# ButtonI2C.net
KiCad netlist of a schematic drawn in EAGLE
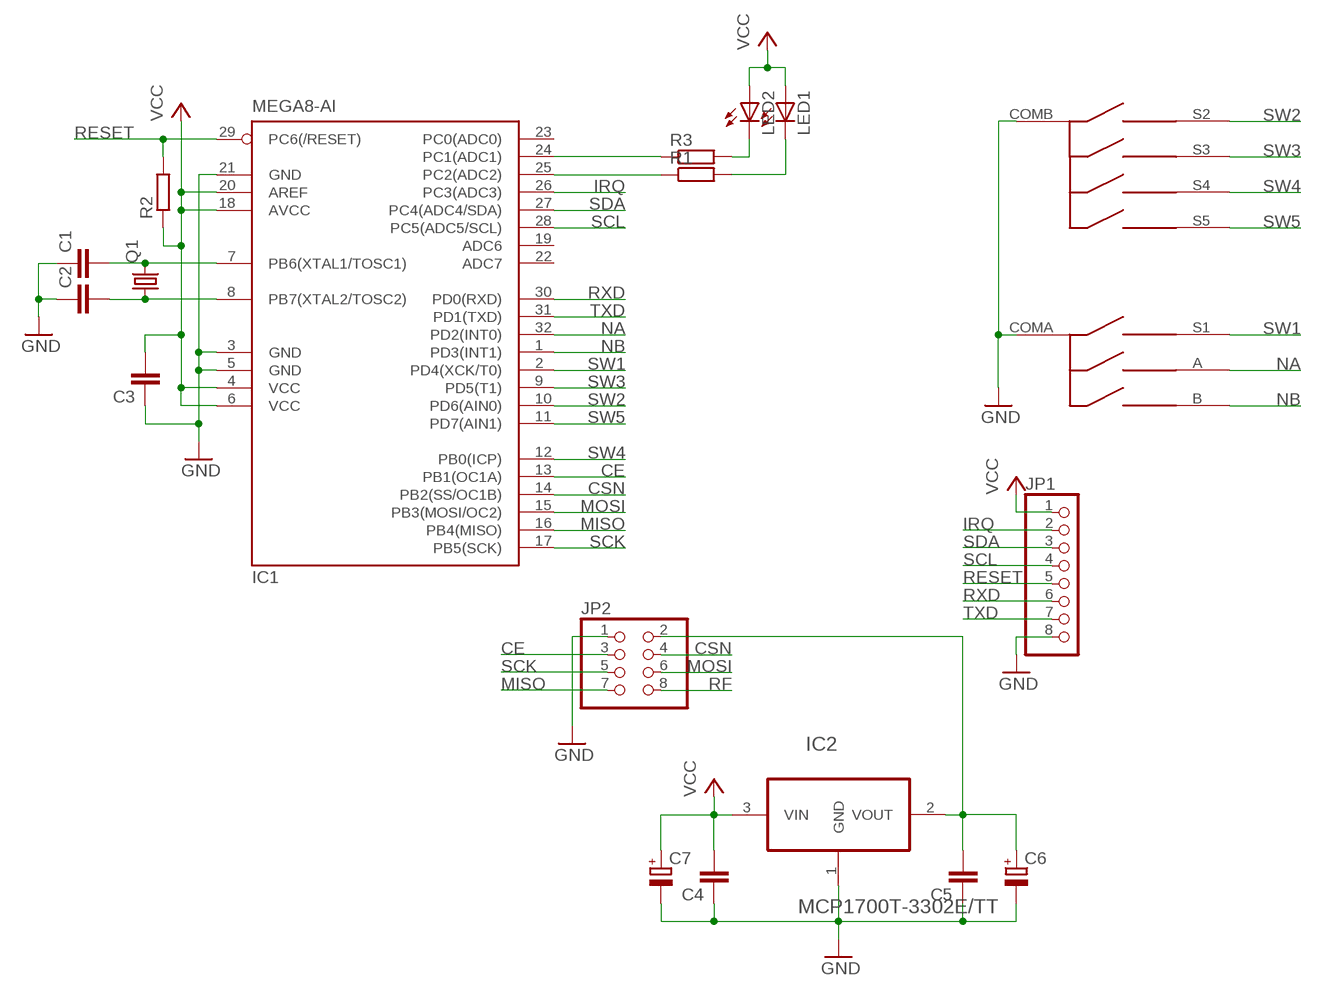
[diagram p0: schematic, sheet 1]

(export (version "E")
  (design (tool "Eeschema 10.0.6"))
  (components
    (comp (ref "C1")
      (value "C-EUC0805K")
      (footprint "eagle-import:C0805K")
      (libsource (lib "eagle-import") (part "C-EUC0805K"))
    )
    (comp (ref "C2")
      (value "C-EUC0805K")
      (footprint "eagle-import:C0805K")
      (libsource (lib "eagle-import") (part "C-EUC0805K"))
    )
    (comp (ref "C3")
      (value "C-EUC0805K")
      (footprint "eagle-import:C0805K")
      (libsource (lib "eagle-import") (part "C-EUC0805K"))
    )
    (comp (ref "C4")
      (value "C-EUC0805K")
      (footprint "eagle-import:C0805K")
      (libsource (lib "eagle-import") (part "C-EUC0805K"))
    )
    (comp (ref "C5")
      (value "C-EUC0805K")
      (footprint "eagle-import:C0805K")
      (libsource (lib "eagle-import") (part "C-EUC0805K"))
    )
    (comp (ref "C6")
      (value "CPOL-EUE2.5-6")
      (footprint "eagle-import:E2,5-6")
      (libsource (lib "eagle-import") (part "CPOL-EUE2.5-6"))
    )
    (comp (ref "C7")
      (value "CPOL-EUE2.5-6")
      (footprint "eagle-import:E2,5-6")
      (libsource (lib "eagle-import") (part "CPOL-EUE2.5-6"))
    )
    (comp (ref "IC1")
      (value "MEGA8-AI")
      (footprint "eagle-import:TQFP32-08")
      (fields (field (name "MPN") "ATMEGA8-16AU"))
      (libsource (lib "eagle-import") (part "MEGA8-AI"))
    )
    (comp (ref "IC2")
      (value "MCP1700T-3302E/TT")
      (footprint "eagle-import:SOT95P237X112-3N")
      (libsource (lib "eagle-import") (part "MCP1700T-3302E/TT"))
    )
    (comp (ref "JP1")
      (value "PINHD-1X8")
      (footprint "eagle-import:1X08")
      (libsource (lib "eagle-import") (part "PINHD-1X8"))
    )
    (comp (ref "JP2")
      (value "PINHD-2X4")
      (footprint "eagle-import:2X04")
      (libsource (lib "eagle-import") (part "PINHD-2X4"))
    )
    (comp (ref "LED1")
      (value "LEDCHIPLED_0805")
      (footprint "eagle-import:CHIPLED_0805")
      (libsource (lib "eagle-import") (part "LEDCHIPLED_0805"))
    )
    (comp (ref "LED2")
      (value "LEDCHIPLED_0805")
      (footprint "eagle-import:CHIPLED_0805")
      (libsource (lib "eagle-import") (part "LEDCHIPLED_0805"))
    )
    (comp (ref "Q1")
      (value "CRYSTALHC49UP")
      (footprint "eagle-import:HC49UP")
      (libsource (lib "eagle-import") (part "CRYSTALHC49UP"))
    )
    (comp (ref "R1")
      (value "R-EU_M0805")
      (footprint "eagle-import:M0805")
      (libsource (lib "eagle-import") (part "R-EU_M0805"))
    )
    (comp (ref "R2")
      (value "R-EU_M0805")
      (footprint "eagle-import:M0805")
      (libsource (lib "eagle-import") (part "R-EU_M0805"))
    )
    (comp (ref "R3")
      (value "R-EU_M0805")
      (footprint "eagle-import:M0805")
      (libsource (lib "eagle-import") (part "R-EU_M0805"))
    )
    (comp (ref "U$1")
      (value "ANO-I1B-M1B-O2B-S-Z")
      (footprint "eagle-import:ANO-I1B-M1B-O2B-S-Z")
      (libsource (lib "eagle-import") (part "ANO-I1B-M1B-O2B-S-Z"))
    )
  )
  (nets
    (net (code "1") (name "/CE") (class "Default")
      (node (ref "IC1") (pin "13") (pinfunction "PB1(OC1A)_13") (pintype "bidirectional"))
      (node (ref "JP2") (pin "3") (pinfunction "3_3") (pintype "passive"))
    )
    (net (code "2") (name "/CSN") (class "Default")
      (node (ref "IC1") (pin "14") (pinfunction "PB2(SS/OC1B)_14") (pintype "bidirectional"))
      (node (ref "JP2") (pin "4") (pinfunction "4_4") (pintype "passive"))
    )
    (net (code "3") (name "/IRQ") (class "Default")
      (node (ref "IC1") (pin "26") (pinfunction "PC3(ADC3)_26") (pintype "bidirectional"))
      (node (ref "JP1") (pin "2") (pinfunction "2_2") (pintype "passive"))
    )
    (net (code "4") (name "/MISO") (class "Default")
      (node (ref "IC1") (pin "16") (pinfunction "PB4(MISO)_16") (pintype "bidirectional"))
      (node (ref "JP2") (pin "7") (pinfunction "7_7") (pintype "passive"))
    )
    (net (code "5") (name "/MOSI") (class "Default")
      (node (ref "IC1") (pin "15") (pinfunction "PB3(MOSI/OC2)_15") (pintype "bidirectional"))
      (node (ref "JP2") (pin "6") (pinfunction "6_6") (pintype "passive"))
    )
    (net (code "6") (name "/NA") (class "Default")
      (node (ref "IC1") (pin "32") (pinfunction "PD2(INT0)_32") (pintype "bidirectional"))
      (node (ref "U$1") (pin "A") (pinfunction "A_A") (pintype "bidirectional"))
    )
    (net (code "7") (name "/NB") (class "Default")
      (node (ref "IC1") (pin "1") (pinfunction "PD3(INT1)_1") (pintype "bidirectional"))
      (node (ref "U$1") (pin "B") (pinfunction "B_B") (pintype "bidirectional"))
    )
    (net (code "8") (name "/RESET") (class "Default")
      (node (ref "IC1") (pin "29") (pinfunction "PC6(/RESET)_29") (pintype "bidirectional"))
      (node (ref "JP1") (pin "5") (pinfunction "5_5") (pintype "passive"))
      (node (ref "R2") (pin "2") (pinfunction "2_2") (pintype "passive"))
    )
    (net (code "9") (name "/RF") (class "Default")
      (node (ref "JP2") (pin "8") (pinfunction "8_8") (pintype "passive"))
    )
    (net (code "10") (name "/RXD") (class "Default")
      (node (ref "IC1") (pin "30") (pinfunction "PD0(RXD)_30") (pintype "bidirectional"))
      (node (ref "JP1") (pin "6") (pinfunction "6_6") (pintype "passive"))
    )
    (net (code "11") (name "/SCK") (class "Default")
      (node (ref "IC1") (pin "17") (pinfunction "PB5(SCK)_17") (pintype "bidirectional"))
      (node (ref "JP2") (pin "5") (pinfunction "5_5") (pintype "passive"))
    )
    (net (code "12") (name "/SCL") (class "Default")
      (node (ref "IC1") (pin "28") (pinfunction "PC5(ADC5/SCL)_28") (pintype "bidirectional"))
      (node (ref "JP1") (pin "4") (pinfunction "4_4") (pintype "passive"))
    )
    (net (code "13") (name "/SDA") (class "Default")
      (node (ref "IC1") (pin "27") (pinfunction "PC4(ADC4/SDA)_27") (pintype "bidirectional"))
      (node (ref "JP1") (pin "3") (pinfunction "3_3") (pintype "passive"))
    )
    (net (code "14") (name "/SW1") (class "Default")
      (node (ref "IC1") (pin "2") (pinfunction "PD4(XCK/T0)_2") (pintype "bidirectional"))
      (node (ref "U$1") (pin "S1") (pinfunction "S1_S1") (pintype "bidirectional"))
    )
    (net (code "15") (name "/SW2") (class "Default")
      (node (ref "IC1") (pin "10") (pinfunction "PD6(AIN0)_10") (pintype "bidirectional"))
      (node (ref "U$1") (pin "S2") (pinfunction "S2_S2") (pintype "bidirectional"))
    )
    (net (code "16") (name "/SW3") (class "Default")
      (node (ref "IC1") (pin "9") (pinfunction "PD5(T1)_9") (pintype "bidirectional"))
      (node (ref "U$1") (pin "S3") (pinfunction "S3_S3") (pintype "bidirectional"))
    )
    (net (code "17") (name "/SW4") (class "Default")
      (node (ref "IC1") (pin "12") (pinfunction "PB0(ICP)_12") (pintype "bidirectional"))
      (node (ref "U$1") (pin "S4") (pinfunction "S4_S4") (pintype "bidirectional"))
    )
    (net (code "18") (name "/SW5") (class "Default")
      (node (ref "IC1") (pin "11") (pinfunction "PD7(AIN1)_11") (pintype "bidirectional"))
      (node (ref "U$1") (pin "S5") (pinfunction "S5_S5") (pintype "bidirectional"))
    )
    (net (code "19") (name "/TXD") (class "Default")
      (node (ref "IC1") (pin "31") (pinfunction "PD1(TXD)_31") (pintype "bidirectional"))
      (node (ref "JP1") (pin "7") (pinfunction "7_7") (pintype "passive"))
    )
    (net (code "20") (name "GND") (class "Default")
      (node (ref "C1") (pin "1") (pinfunction "1_1") (pintype "passive"))
      (node (ref "C2") (pin "1") (pinfunction "1_1") (pintype "passive"))
      (node (ref "C3") (pin "1") (pinfunction "1_1") (pintype "passive"))
      (node (ref "C4") (pin "1") (pinfunction "1_1") (pintype "passive"))
      (node (ref "C5") (pin "1") (pinfunction "1_1") (pintype "passive"))
      (node (ref "C6") (pin "-") (pinfunction "-_-") (pintype "passive"))
      (node (ref "C7") (pin "-") (pinfunction "-_-") (pintype "passive"))
      (node (ref "IC1") (pin "21") (pinfunction "GND_21") (pintype "power_in"))
      (node (ref "IC1") (pin "3") (pinfunction "GND_3") (pintype "power_in"))
      (node (ref "IC1") (pin "5") (pinfunction "GND_5") (pintype "power_in"))
      (node (ref "IC2") (pin "1") (pinfunction "GND_1") (pintype "passive"))
      (node (ref "JP1") (pin "8") (pinfunction "8_8") (pintype "passive"))
      (node (ref "JP2") (pin "1") (pinfunction "1_1") (pintype "passive"))
      (node (ref "U$1") (pin "COMA") (pinfunction "COMA_COMA") (pintype "bidirectional"))
      (node (ref "U$1") (pin "COMB") (pinfunction "COMB_COMB") (pintype "bidirectional"))
    )
    (net (code "21") (name "Net-(IC1-PB6(XTAL1{slash}TOSC1))") (class "Default")
      (node (ref "C1") (pin "2") (pinfunction "2_2") (pintype "passive"))
      (node (ref "IC1") (pin "7") (pinfunction "PB6(XTAL1/TOSC1)_7") (pintype "bidirectional"))
      (node (ref "Q1") (pin "2") (pinfunction "2_2") (pintype "passive"))
    )
    (net (code "22") (name "Net-(IC1-PB7(XTAL2{slash}TOSC2))") (class "Default")
      (node (ref "C2") (pin "2") (pinfunction "2_2") (pintype "passive"))
      (node (ref "IC1") (pin "8") (pinfunction "PB7(XTAL2/TOSC2)_8") (pintype "bidirectional"))
      (node (ref "Q1") (pin "1") (pinfunction "1_1") (pintype "passive"))
    )
    (net (code "23") (name "Net-(IC1-PC1(ADC1))") (class "Default")
      (node (ref "IC1") (pin "24") (pinfunction "PC1(ADC1)_24") (pintype "bidirectional"))
      (node (ref "R3") (pin "1") (pinfunction "1_1") (pintype "passive"))
    )
    (net (code "24") (name "Net-(IC1-PC2(ADC2))") (class "Default")
      (node (ref "IC1") (pin "25") (pinfunction "PC2(ADC2)_25") (pintype "bidirectional"))
      (node (ref "R1") (pin "1") (pinfunction "1_1") (pintype "passive"))
    )
    (net (code "25") (name "Net-(IC2-VOUT)") (class "Default")
      (node (ref "C5") (pin "2") (pinfunction "2_2") (pintype "passive"))
      (node (ref "C6") (pin "+") (pinfunction "+_+") (pintype "passive"))
      (node (ref "IC2") (pin "2") (pinfunction "VOUT_2") (pintype "passive"))
      (node (ref "JP2") (pin "2") (pinfunction "2_2") (pintype "passive"))
    )
    (net (code "26") (name "Net-(LED1-PadC)") (class "Default")
      (node (ref "LED1") (pin "C") (pinfunction "C_C") (pintype "passive"))
      (node (ref "R1") (pin "2") (pinfunction "2_2") (pintype "passive"))
    )
    (net (code "27") (name "Net-(LED2-PadC)") (class "Default")
      (node (ref "LED2") (pin "C") (pinfunction "C_C") (pintype "passive"))
      (node (ref "R3") (pin "2") (pinfunction "2_2") (pintype "passive"))
    )
    (net (code "28") (name "VCC") (class "Default")
      (node (ref "C3") (pin "2") (pinfunction "2_2") (pintype "passive"))
      (node (ref "C4") (pin "2") (pinfunction "2_2") (pintype "passive"))
      (node (ref "C7") (pin "+") (pinfunction "+_+") (pintype "passive"))
      (node (ref "IC1") (pin "18") (pinfunction "AVCC_18") (pintype "power_in"))
      (node (ref "IC1") (pin "20") (pinfunction "AREF_20") (pintype "passive"))
      (node (ref "IC1") (pin "4") (pinfunction "VCC_4") (pintype "power_in"))
      (node (ref "IC1") (pin "6") (pinfunction "VCC_6") (pintype "power_in"))
      (node (ref "IC2") (pin "3") (pinfunction "VIN_3") (pintype "input"))
      (node (ref "JP1") (pin "1") (pinfunction "1_1") (pintype "passive"))
      (node (ref "LED1") (pin "A") (pinfunction "A_A") (pintype "passive"))
      (node (ref "LED2") (pin "A") (pinfunction "A_A") (pintype "passive"))
      (node (ref "R2") (pin "1") (pinfunction "1_1") (pintype "passive"))
    )
    (net (code "29") (name "unconnected-(IC1-ADC6-Pad19)") (class "Default")
      (node (ref "IC1") (pin "19") (pinfunction "ADC6_19") (pintype "bidirectional"))
    )
    (net (code "30") (name "unconnected-(IC1-ADC7-Pad22)") (class "Default")
      (node (ref "IC1") (pin "22") (pinfunction "ADC7_22") (pintype "bidirectional"))
    )
    (net (code "31") (name "unconnected-(IC1-PC0(ADC0)-Pad23)") (class "Default")
      (node (ref "IC1") (pin "23") (pinfunction "PC0(ADC0)_23") (pintype "bidirectional"))
    )
  )
)
